# Slave_2_button.net
KiCad netlist of a schematic drawn in Altium Designer
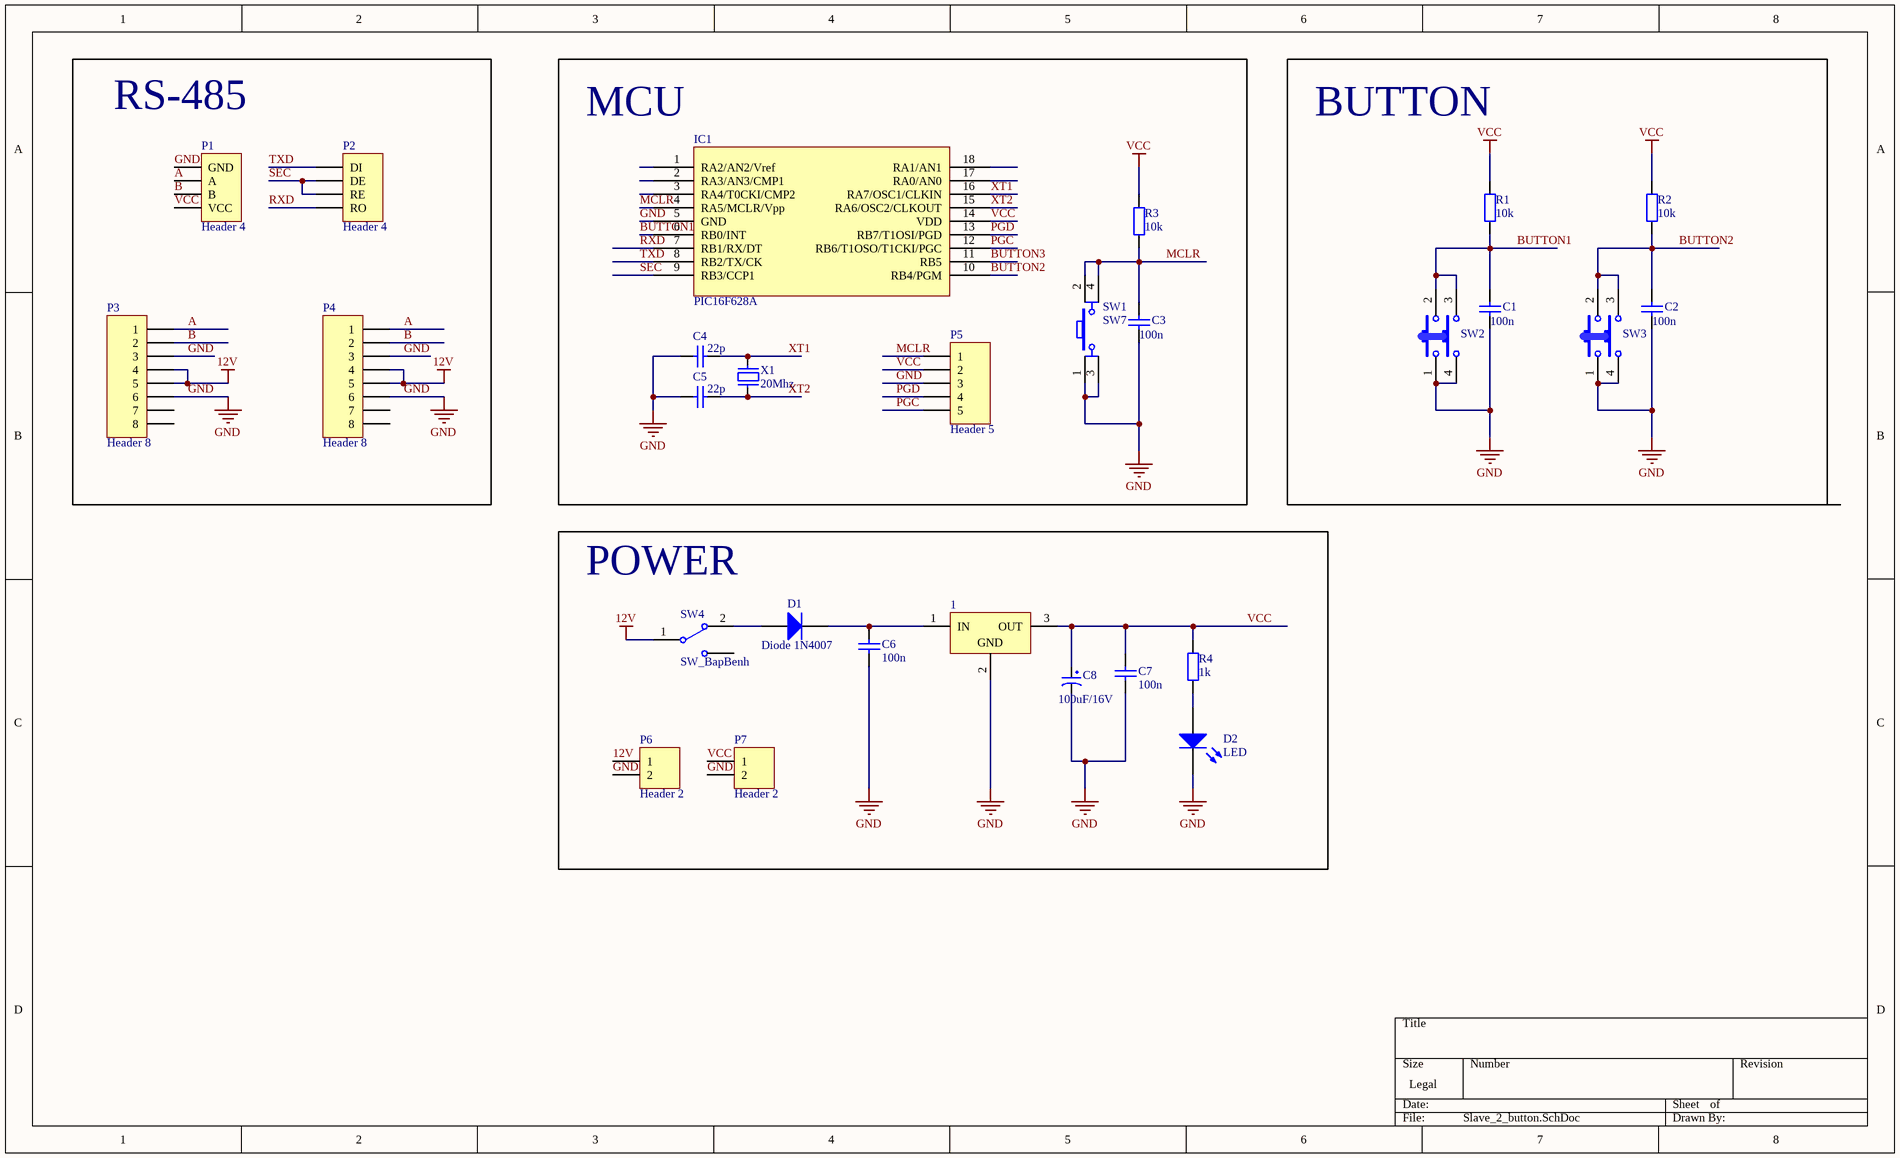
[diagram p0: Slave_2_button.SchDoc]

(export (version "E")
  (design (tool "Eeschema 10.0.6"))
  (components
    (comp (ref "1")
      (value "L78M05CP")
      (footprint "QTO-220")
      (description "Positive Voltage Regulator")
      (fields (field (name "PUBLISHER") "Altium Limited"))
      (libsource (lib "syhaunguyen") (part "L78M05CP"))
    )
    (comp (ref "C1")
      (value "100n")
      (footprint "Cap Non-Pol 3mm")
      (description "Capacitor")
      (fields (field (name "Comment") "Capacitor Ceramic") (field (name "PUBLISHER") "Altium Limited"))
      (libsource (lib "THG") (part "CapSMD"))
    )
    (comp (ref "C2")
      (value "100n")
      (footprint "Cap Non-Pol 3mm")
      (description "Capacitor")
      (fields (field (name "Comment") "Capacitor Ceramic") (field (name "PUBLISHER") "Altium Limited"))
      (libsource (lib "THG") (part "CapSMD"))
    )
    (comp (ref "C3")
      (value "100n")
      (footprint "Cap Non-Pol 3mm")
      (description "Capacitor")
      (fields (field (name "Comment") "Capacitor Ceramic") (field (name "PUBLISHER") "Altium Limited"))
      (libsource (lib "THG") (part "CapSMD"))
    )
    (comp (ref "C4")
      (value "22p")
      (footprint "Cap Non-Pol 3mm")
      (description "Non-polarized Capacitor")
      (fields (field (name "Comment") "Cap Non-pol") (field (name "PUBLISHER") "Altium Limited"))
      (libsource (lib "THG") (part "Cap Non-pol"))
    )
    (comp (ref "C5")
      (value "22p")
      (footprint "Cap Non-Pol 3mm")
      (description "Non-polarized Capacitor")
      (fields (field (name "Comment") "Cap Non-pol") (field (name "PUBLISHER") "Altium Limited"))
      (libsource (lib "THG") (part "Cap Non-pol"))
    )
    (comp (ref "C6")
      (value "100n")
      (footprint "Cap Non-Pol 3mm")
      (description "Non-polarized Capacitor")
      (fields (field (name "Comment") "Cap Non-pol") (field (name "PUBLISHER") "Altium Limited"))
      (libsource (lib "THG") (part "Cap Non-pol"))
    )
    (comp (ref "C7")
      (value "100n")
      (footprint "Cap Non-Pol 3mm")
      (description "Non-polarized Capacitor")
      (fields (field (name "Comment") "Cap Non-pol") (field (name "PUBLISHER") "Altium Limited"))
      (libsource (lib "THG") (part "Cap Non-pol"))
    )
    (comp (ref "C8")
      (value "100uF/16V")
      (footprint "CP1.5/3.4")
      (description "Cap 100uF/35V - 470uF/16V")
      (libsource (lib "syhaunguyen") (part "CP3"))
    )
    (comp (ref "D1")
      (value "Diode 1N4007")
      (footprint "DO-41")
      (description "1 Amp General Purpose Rectifier")
      (fields (field (name "PUBLISHER") "Altium Limited"))
      (libsource (lib "hphonglib") (part "Diode 1N4007"))
    )
    (comp (ref "D2")
      (value "LED")
      (footprint "LED-5mm RED")
      (description "Typical LED")
      (fields (field (name "PUBLISHER") "Altium Limited"))
      (libsource (lib "THG") (part "LED"))
    )
    (comp (ref "IC1")
      (value "PIC16F628A")
      (footprint "DIP18/W0.3")
      (libsource (lib "THG") (part "PIC16F628A"))
    )
    (comp (ref "P1")
      (value "Header 4")
      (footprint "HDR1X4")
      (description "Header, 4-Pin")
      (fields (field (name "PUBLISHER") "Altium Limited"))
      (libsource (lib "Miscellaneous Connectors") (part "Header 4"))
    )
    (comp (ref "P2")
      (value "Header 4")
      (footprint "HDR1X4")
      (description "Header, 4-Pin")
      (fields (field (name "PUBLISHER") "Altium Limited"))
      (libsource (lib "Miscellaneous Connectors") (part "Header 4"))
    )
    (comp (ref "P3")
      (value "Header 8")
      (footprint "RJ11")
      (description "Header, 8-Pin")
      (fields (field (name "PUBLISHER") "Altium Limited"))
      (libsource (lib "THG") (part "Header 8"))
    )
    (comp (ref "P4")
      (value "Header 8")
      (footprint "RJ11")
      (description "Header, 8-Pin")
      (fields (field (name "PUBLISHER") "Altium Limited"))
      (libsource (lib "THG") (part "Header 8"))
    )
    (comp (ref "P5")
      (value "Header 5")
      (footprint "Header 5")
      (description "Header, 5-Pin")
      (fields (field (name "PUBLISHER") "Altium Limited"))
      (libsource (lib "THG") (part "Header 5"))
    )
    (comp (ref "P6")
      (value "Header 2")
      (footprint "HDR1X2")
      (description "Header, 2-Pin")
      (fields (field (name "PUBLISHER") "Altium Limited"))
      (libsource (lib "Miscellaneous Connectors") (part "Header 2"))
    )
    (comp (ref "P7")
      (value "Header 2")
      (footprint "HDR1X2")
      (description "Header, 2-Pin")
      (fields (field (name "PUBLISHER") "Altium Limited"))
      (libsource (lib "Miscellaneous Connectors") (part "Header 2"))
    )
    (comp (ref "R1")
      (value "10k")
      (footprint "RESISTOR 1/4W")
      (description "RES_0805")
      (fields (field (name "Comment") "RES_SMD_0805") (field (name "PUBLISHER") "Altium Limited"))
      (libsource (lib "THG") (part "RES_SMD_0805"))
    )
    (comp (ref "R2")
      (value "10k")
      (footprint "RESISTOR 1/4W")
      (description "RES_0805")
      (fields (field (name "Comment") "RES_SMD_0805") (field (name "PUBLISHER") "Altium Limited"))
      (libsource (lib "THG") (part "RES_SMD_0805"))
    )
    (comp (ref "R3")
      (value "10k")
      (footprint "RESISTOR 1/4W")
      (description "RES_0805")
      (fields (field (name "Comment") "RES_SMD_0805") (field (name "PUBLISHER") "Altium Limited"))
      (libsource (lib "THG") (part "RES_SMD_0805"))
    )
    (comp (ref "R4")
      (value "1k")
      (footprint "RESISTOR 1/4W")
      (description "RES_0805")
      (fields (field (name "Comment") "RES_SMD_0805") (field (name "PUBLISHER") "Altium Limited"))
      (libsource (lib "THG") (part "RES_SMD_0805"))
    )
    (comp (ref "SW1")
      (value "SW7")
      (footprint "SW4")
      (description "Switch button 4 pin")
      (libsource (lib "syhaunguyen") (part "SW4"))
    )
    (comp (ref "SW2")
      (value "SW-4P-B")
      (footprint "SW-4P-B")
      (description "Switch Big 4 Pin")
      (fields (field (name "PUBLISHER") "Altium Limited"))
      (libsource (lib "hphonglib") (part "SW-4PIN-BIG"))
    )
    (comp (ref "SW3")
      (value "SW-4P-B")
      (footprint "SW-4P-B")
      (description "Switch Big 4 Pin")
      (fields (field (name "PUBLISHER") "Altium Limited"))
      (libsource (lib "hphonglib") (part "SW-4PIN-BIG"))
    )
    (comp (ref "SW4")
      (value "SW_BapBenh")
      (footprint "SW_Bapbenh")
      (libsource (lib "THG") (part "SW_BapBenh"))
    )
    (comp (ref "X1")
      (value "20Mhz")
      (footprint "XT2")
      (description "Crystal For all Crystal 2pin.")
      (libsource (lib "syhaunguyen") (part "XT2"))
    )
  )
  (nets
    (net (code "1") (name "/A") (class "Default")
      (node (ref "P1") (pin "2") (pinfunction "A_2") (pintype "passive"))
      (node (ref "P3") (pin "1") (pinfunction "1_1") (pintype "passive"))
      (node (ref "P4") (pin "1") (pinfunction "1_1") (pintype "passive"))
    )
    (net (code "2") (name "/B") (class "Default")
      (node (ref "P1") (pin "3") (pinfunction "B_3") (pintype "passive"))
      (node (ref "P3") (pin "2") (pinfunction "2_2") (pintype "passive"))
      (node (ref "P4") (pin "2") (pinfunction "2_2") (pintype "passive"))
    )
    (net (code "3") (name "/BUTTON1") (class "Default")
      (node (ref "C1") (pin "2") (pinfunction "2_2") (pintype "passive"))
      (node (ref "IC1") (pin "6") (pinfunction "RB0/INT_6") (pintype "passive"))
      (node (ref "R1") (pin "1") (pinfunction "1_1") (pintype "passive"))
      (node (ref "SW2") (pin "2") (pinfunction "2_2") (pintype "passive"))
      (node (ref "SW2") (pin "3") (pinfunction "3_3") (pintype "passive"))
    )
    (net (code "4") (name "/BUTTON2") (class "Default")
      (node (ref "C2") (pin "2") (pinfunction "2_2") (pintype "passive"))
      (node (ref "IC1") (pin "10") (pinfunction "RB4/PGM_10") (pintype "passive"))
      (node (ref "R2") (pin "1") (pinfunction "1_1") (pintype "passive"))
      (node (ref "SW3") (pin "2") (pinfunction "2_2") (pintype "passive"))
      (node (ref "SW3") (pin "3") (pinfunction "3_3") (pintype "passive"))
    )
    (net (code "5") (name "/BUTTON3") (class "Default")
      (node (ref "IC1") (pin "11") (pinfunction "RB5_11") (pintype "passive"))
    )
    (net (code "6") (name "/MCLR") (class "Default")
      (node (ref "C3") (pin "2") (pinfunction "2_2") (pintype "passive"))
      (node (ref "IC1") (pin "4") (pinfunction "RA5/MCLR/Vpp_4") (pintype "passive"))
      (node (ref "P5") (pin "1") (pinfunction "1_1") (pintype "passive"))
      (node (ref "R3") (pin "1") (pinfunction "1_1") (pintype "passive"))
      (node (ref "SW1") (pin "2") (pintype "passive"))
      (node (ref "SW1") (pin "4") (pintype "passive"))
    )
    (net (code "7") (name "/PGC") (class "Default")
      (node (ref "IC1") (pin "12") (pinfunction "RB6/T1OSO/T1CKI/PGC_12") (pintype "passive"))
      (node (ref "P5") (pin "5") (pinfunction "5_5") (pintype "passive"))
    )
    (net (code "8") (name "/PGD") (class "Default")
      (node (ref "IC1") (pin "13") (pinfunction "RB7/T1OSI/PGD_13") (pintype "passive"))
      (node (ref "P5") (pin "4") (pinfunction "4_4") (pintype "passive"))
    )
    (net (code "9") (name "/RXD") (class "Default")
      (node (ref "IC1") (pin "7") (pinfunction "RB1/RX/DT_7") (pintype "passive"))
      (node (ref "P2") (pin "4") (pinfunction "VCC_4") (pintype "passive"))
    )
    (net (code "10") (name "/SEC") (class "Default")
      (node (ref "IC1") (pin "9") (pinfunction "RB3/CCP1_9") (pintype "passive"))
      (node (ref "P2") (pin "2") (pinfunction "A_2") (pintype "passive"))
      (node (ref "P2") (pin "3") (pinfunction "B_3") (pintype "passive"))
    )
    (net (code "11") (name "/TXD") (class "Default")
      (node (ref "IC1") (pin "8") (pinfunction "RB2/TX/CK_8") (pintype "passive"))
      (node (ref "P2") (pin "1") (pinfunction "GND_1") (pintype "passive"))
    )
    (net (code "12") (name "/XT1") (class "Default")
      (node (ref "C4") (pin "1") (pinfunction "1_1") (pintype "passive"))
      (node (ref "IC1") (pin "16") (pinfunction "RA7/OSC1/CLKIN_16") (pintype "passive"))
      (node (ref "X1") (pin "2") (pinfunction "2_2") (pintype "passive"))
    )
    (net (code "13") (name "/XT2") (class "Default")
      (node (ref "C5") (pin "1") (pinfunction "1_1") (pintype "passive"))
      (node (ref "IC1") (pin "15") (pinfunction "RA6/OSC2/CLKOUT_15") (pintype "passive"))
      (node (ref "X1") (pin "1") (pinfunction "1_1") (pintype "passive"))
    )
    (net (code "14") (name "12V") (class "Default")
      (node (ref "P3") (pin "4") (pinfunction "4_4") (pintype "passive"))
      (node (ref "P3") (pin "5") (pinfunction "5_5") (pintype "passive"))
      (node (ref "P4") (pin "4") (pinfunction "4_4") (pintype "passive"))
      (node (ref "P4") (pin "5") (pinfunction "5_5") (pintype "passive"))
      (node (ref "P6") (pin "1") (pinfunction "1_1") (pintype "passive"))
      (node (ref "SW4") (pin "1") (pinfunction "1_1") (pintype "passive"))
    )
    (net (code "15") (name "GND") (class "Default")
      (node (ref "1") (pin "2") (pinfunction "GND_2") (pintype "power_in"))
      (node (ref "C1") (pin "1") (pinfunction "1_1") (pintype "passive"))
      (node (ref "C2") (pin "1") (pinfunction "1_1") (pintype "passive"))
      (node (ref "C3") (pin "1") (pinfunction "1_1") (pintype "passive"))
      (node (ref "C4") (pin "2") (pinfunction "2_2") (pintype "passive"))
      (node (ref "C5") (pin "2") (pinfunction "2_2") (pintype "passive"))
      (node (ref "C6") (pin "1") (pinfunction "1_1") (pintype "passive"))
      (node (ref "C7") (pin "1") (pinfunction "1_1") (pintype "passive"))
      (node (ref "C8") (pin "2") (pinfunction "2_2") (pintype "passive"))
      (node (ref "D2") (pin "2") (pinfunction "K_2") (pintype "passive"))
      (node (ref "IC1") (pin "5") (pinfunction "GND_5") (pintype "passive"))
      (node (ref "P1") (pin "1") (pinfunction "GND_1") (pintype "passive"))
      (node (ref "P3") (pin "3") (pinfunction "3_3") (pintype "passive"))
      (node (ref "P3") (pin "6") (pinfunction "6_6") (pintype "passive"))
      (node (ref "P4") (pin "3") (pinfunction "3_3") (pintype "passive"))
      (node (ref "P4") (pin "6") (pinfunction "6_6") (pintype "passive"))
      (node (ref "P5") (pin "3") (pinfunction "3_3") (pintype "passive"))
      (node (ref "P6") (pin "2") (pinfunction "2_2") (pintype "passive"))
      (node (ref "P7") (pin "2") (pinfunction "2_2") (pintype "passive"))
      (node (ref "SW1") (pin "1") (pintype "passive"))
      (node (ref "SW1") (pin "3") (pintype "passive"))
      (node (ref "SW2") (pin "1") (pinfunction "1_1") (pintype "passive"))
      (node (ref "SW2") (pin "4") (pinfunction "4_4") (pintype "passive"))
      (node (ref "SW3") (pin "1") (pinfunction "1_1") (pintype "passive"))
      (node (ref "SW3") (pin "4") (pinfunction "4_4") (pintype "passive"))
    )
    (net (code "16") (name "Net-(1-IN)") (class "Default")
      (node (ref "1") (pin "1") (pinfunction "IN_1") (pintype "power_in"))
      (node (ref "C6") (pin "2") (pinfunction "2_2") (pintype "passive"))
      (node (ref "D1") (pin "2") (pinfunction "K_2") (pintype "passive"))
    )
    (net (code "17") (name "Net-(D1-A)") (class "Default")
      (node (ref "D1") (pin "1") (pinfunction "A_1") (pintype "passive"))
      (node (ref "SW4") (pin "2") (pinfunction "2_2") (pintype "passive"))
    )
    (net (code "18") (name "Net-(D2-A)") (class "Default")
      (node (ref "D2") (pin "1") (pinfunction "A_1") (pintype "passive"))
      (node (ref "R4") (pin "1") (pinfunction "1_1") (pintype "passive"))
    )
    (net (code "19") (name "VCC") (class "Default")
      (node (ref "1") (pin "3") (pinfunction "OUT_3") (pintype "power_in"))
      (node (ref "C7") (pin "2") (pinfunction "2_2") (pintype "passive"))
      (node (ref "C8") (pin "1") (pinfunction "1_1") (pintype "passive"))
      (node (ref "IC1") (pin "14") (pinfunction "VDD_14") (pintype "passive"))
      (node (ref "P1") (pin "4") (pinfunction "VCC_4") (pintype "passive"))
      (node (ref "P5") (pin "2") (pinfunction "2_2") (pintype "passive"))
      (node (ref "P7") (pin "1") (pinfunction "1_1") (pintype "passive"))
      (node (ref "R1") (pin "2") (pinfunction "2_2") (pintype "passive"))
      (node (ref "R2") (pin "2") (pinfunction "2_2") (pintype "passive"))
      (node (ref "R3") (pin "2") (pinfunction "2_2") (pintype "passive"))
      (node (ref "R4") (pin "2") (pinfunction "2_2") (pintype "passive"))
    )
    (net (code "20") (name "unconnected-(IC1-RA0{slash}AN0-Pad17)") (class "Default")
      (node (ref "IC1") (pin "17") (pinfunction "RA0/AN0_17") (pintype "passive"))
    )
    (net (code "21") (name "unconnected-(IC1-RA1{slash}AN1-Pad18)") (class "Default")
      (node (ref "IC1") (pin "18") (pinfunction "RA1/AN1_18") (pintype "passive"))
    )
    (net (code "22") (name "unconnected-(IC1-RA2{slash}AN2{slash}Vref-Pad1)") (class "Default")
      (node (ref "IC1") (pin "1") (pinfunction "RA2/AN2/Vref_1") (pintype "passive"))
    )
    (net (code "23") (name "unconnected-(IC1-RA3{slash}AN3{slash}CMP1-Pad2)") (class "Default")
      (node (ref "IC1") (pin "2") (pinfunction "RA3/AN3/CMP1_2") (pintype "passive"))
    )
    (net (code "24") (name "unconnected-(IC1-RA4{slash}T0CKI{slash}CMP2-Pad3)") (class "Default")
      (node (ref "IC1") (pin "3") (pinfunction "RA4/T0CKI/CMP2_3") (pintype "passive"))
    )
    (net (code "25") (name "unconnected-(P3-Pad7)") (class "Default")
      (node (ref "P3") (pin "7") (pinfunction "7_7") (pintype "passive"))
    )
    (net (code "26") (name "unconnected-(P3-Pad8)") (class "Default")
      (node (ref "P3") (pin "8") (pinfunction "8_8") (pintype "passive"))
    )
    (net (code "27") (name "unconnected-(P4-Pad7)") (class "Default")
      (node (ref "P4") (pin "7") (pinfunction "7_7") (pintype "passive"))
    )
    (net (code "28") (name "unconnected-(P4-Pad8)") (class "Default")
      (node (ref "P4") (pin "8") (pinfunction "8_8") (pintype "passive"))
    )
  )
)
